# e-book_schema.net
KiCad netlist of a schematic drawn in EAGLE
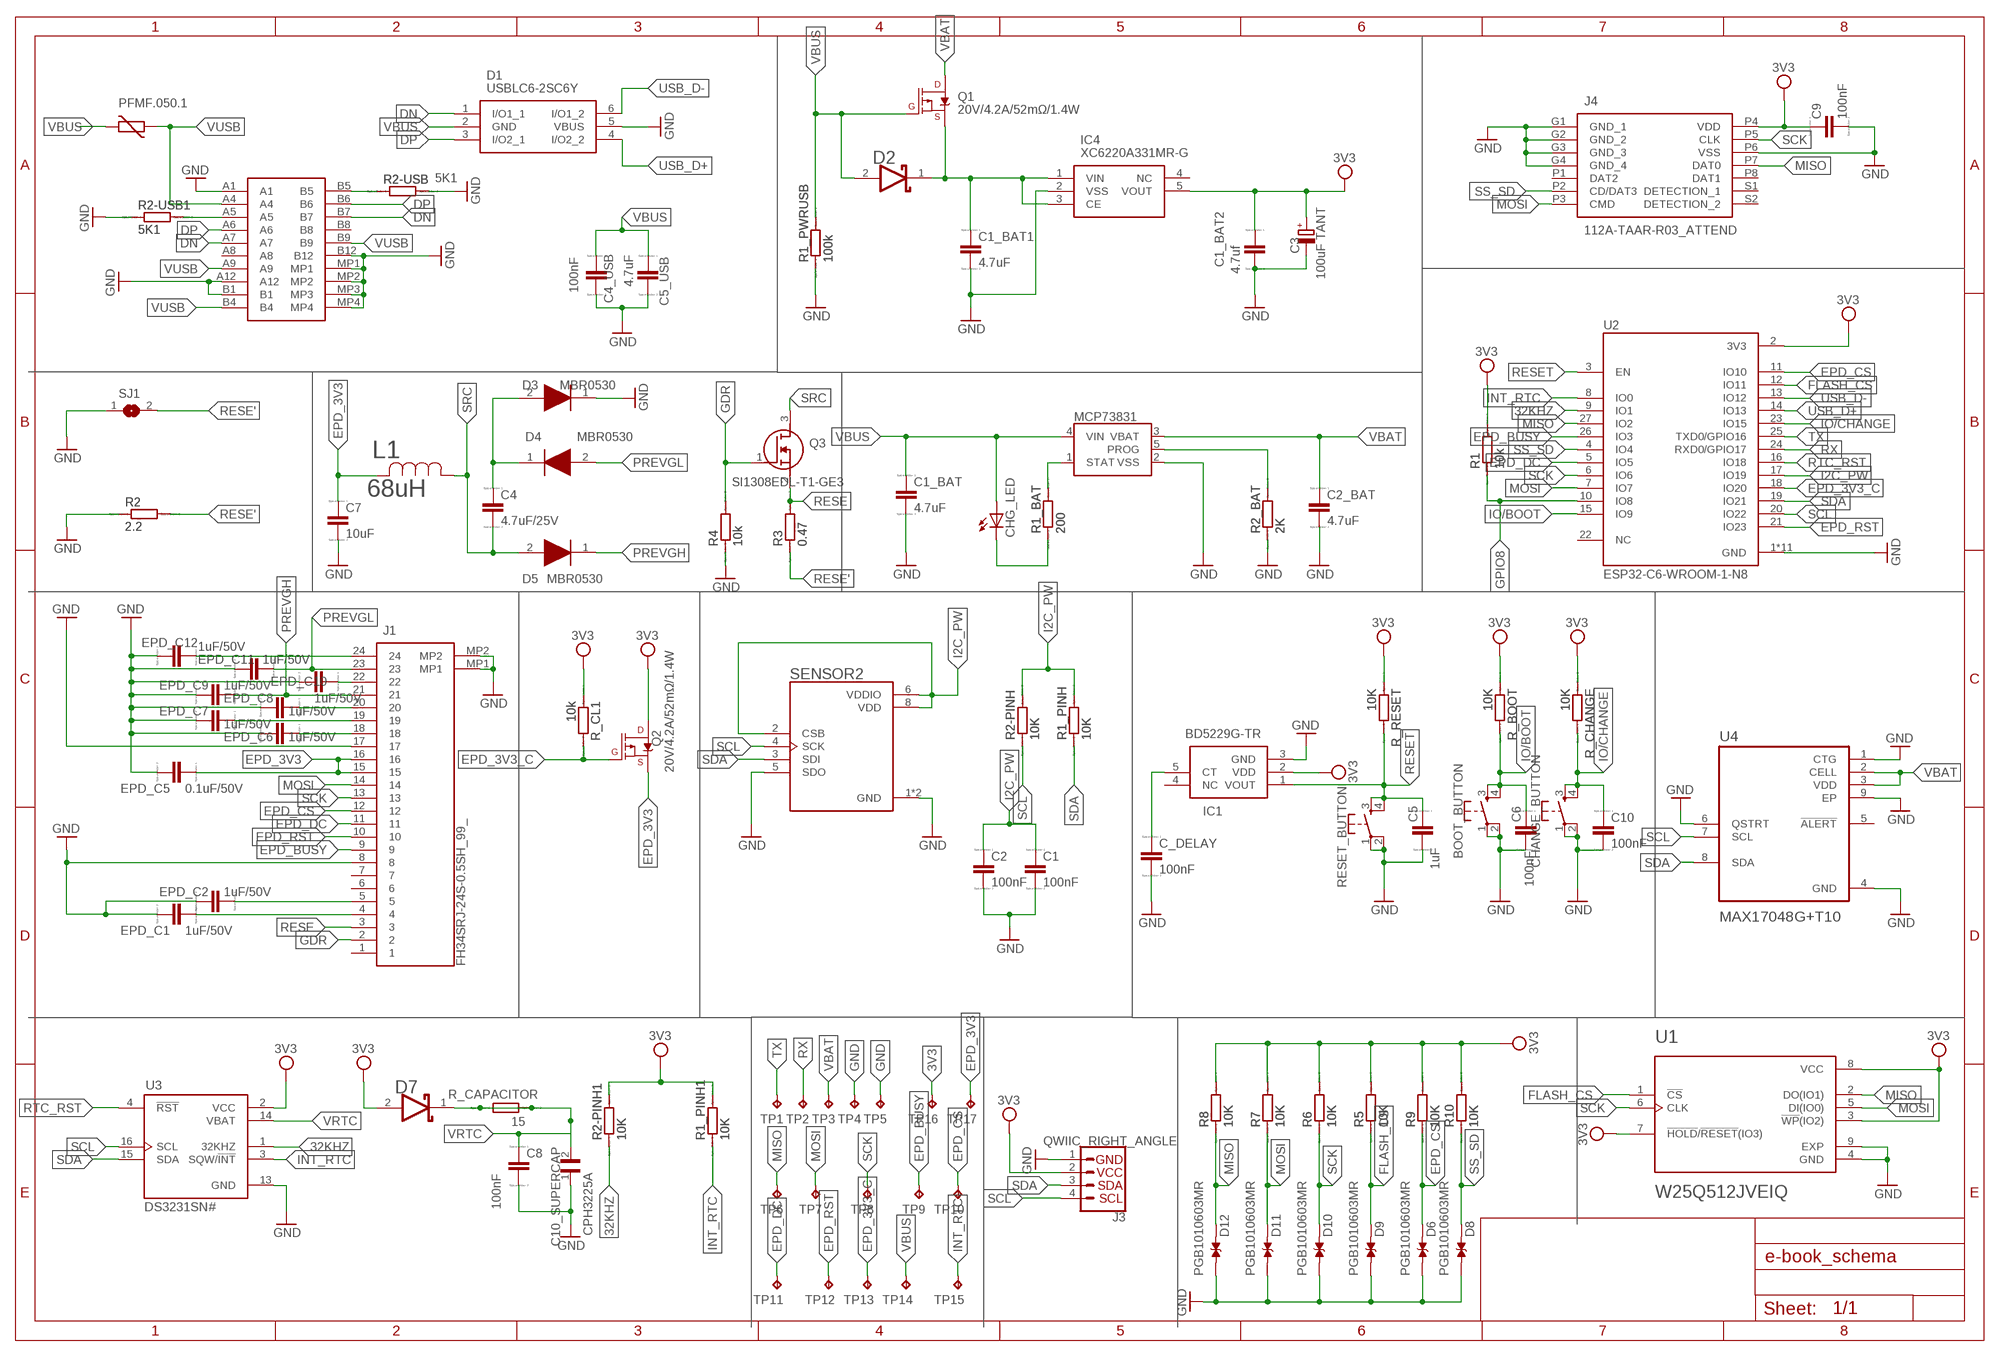
[diagram p0: schematic, sheet 1]

(export (version "E")
  (design (tool "Eeschema 10.0.6"))
  (components
    (comp (ref "BOOT_BUTTON")
      (value "BUTTON_CUSYOMV1")
      (footprint "eagle-import:MYBUTTON")
      (libsource (lib "eagle-import") (part "BUTTON_CUSYOMV1"))
    )
    (comp (ref "C1")
      (value "100nF")
      (footprint "eagle-import:EAGLE-LTSPICE_C0402")
      (libsource (lib "eagle-import") (part "EAGLE-LTSPICE_CC0402"))
    )
    (comp (ref "C1_BAT")
      (value "4.7uF")
      (footprint "eagle-import:EAGLE-LTSPICE_C0402")
      (libsource (lib "eagle-import") (part "EAGLE-LTSPICE_CC0402"))
    )
    (comp (ref "C1_BAT1")
      (value "4.7uF")
      (footprint "eagle-import:EAGLE-LTSPICE_C0402")
      (libsource (lib "eagle-import") (part "EAGLE-LTSPICE_CC0402"))
    )
    (comp (ref "C1_BAT2")
      (value "4.7uf")
      (footprint "eagle-import:EAGLE-LTSPICE_C0402")
      (libsource (lib "eagle-import") (part "EAGLE-LTSPICE_CC0402"))
    )
    (comp (ref "C2")
      (value "100nF")
      (footprint "eagle-import:EAGLE-LTSPICE_C0402")
      (libsource (lib "eagle-import") (part "EAGLE-LTSPICE_CC0402"))
    )
    (comp (ref "C2_BAT")
      (value "4.7uF")
      (footprint "eagle-import:EAGLE-LTSPICE_C0402")
      (libsource (lib "eagle-import") (part "EAGLE-LTSPICE_CC0402"))
    )
    (comp (ref "C3")
      (value "100uF TANT")
      (footprint "eagle-import:RCL_CT3528")
      (libsource (lib "eagle-import") (part "RCL_CPOL-EUCT3528"))
    )
    (comp (ref "C4")
      (value "4.7uF/25V")
      (footprint "eagle-import:EAGLE-LTSPICE_C0402")
      (libsource (lib "eagle-import") (part "EAGLE-LTSPICE_CC0402"))
    )
    (comp (ref "C4_USB")
      (value "100nF")
      (footprint "eagle-import:EAGLE-LTSPICE_C0402")
      (libsource (lib "eagle-import") (part "EAGLE-LTSPICE_CC0402"))
    )
    (comp (ref "C5")
      (value "1uF")
      (footprint "eagle-import:EAGLE-LTSPICE_C0402")
      (libsource (lib "eagle-import") (part "EAGLE-LTSPICE_CC0402"))
    )
    (comp (ref "C5_USB")
      (value "4.7uF")
      (footprint "eagle-import:EAGLE-LTSPICE_C0402")
      (libsource (lib "eagle-import") (part "EAGLE-LTSPICE_CC0402"))
    )
    (comp (ref "C6")
      (value "100nF")
      (footprint "eagle-import:EAGLE-LTSPICE_C0402")
      (libsource (lib "eagle-import") (part "EAGLE-LTSPICE_CC0402"))
    )
    (comp (ref "C7")
      (value "10uF")
      (footprint "eagle-import:EAGLE-LTSPICE_C0402")
      (libsource (lib "eagle-import") (part "EAGLE-LTSPICE_CC0402"))
    )
    (comp (ref "C8")
      (value "100nF")
      (footprint "eagle-import:EAGLE-LTSPICE_C0402")
      (libsource (lib "eagle-import") (part "EAGLE-LTSPICE_CC0402"))
    )
    (comp (ref "C9")
      (value "100nF")
      (footprint "eagle-import:EAGLE-LTSPICE_C0402")
      (libsource (lib "eagle-import") (part "EAGLE-LTSPICE_CC0402"))
    )
    (comp (ref "C10")
      (value "100nF")
      (footprint "eagle-import:EAGLE-LTSPICE_C0402")
      (libsource (lib "eagle-import") (part "EAGLE-LTSPICE_CC0402"))
    )
    (comp (ref "C10_SUPERCAP")
      (value "CPH3225A")
      (footprint "eagle-import:CAPCP3225X100N")
      (fields (field (name "MF") "Seiko Instruments"))
      (libsource (lib "eagle-import") (part "CPH3225A"))
    )
    (comp (ref "CHANGE_BUTTON")
      (value "BUTTON_CUSYOMV1")
      (footprint "eagle-import:MYBUTTON")
      (libsource (lib "eagle-import") (part "BUTTON_CUSYOMV1"))
    )
    (comp (ref "CHG_LED")
      (value "ADAFRUIT_LEDCHIP-LED0603")
      (footprint "eagle-import:ADAFRUIT_CHIP-LED0603")
      (libsource (lib "eagle-import") (part "ADAFRUIT_LEDCHIP-LED0603"))
    )
    (comp (ref "C_DELAY")
      (value "100nF")
      (footprint "eagle-import:EAGLE-LTSPICE_C0402")
      (libsource (lib "eagle-import") (part "EAGLE-LTSPICE_CC0402"))
    )
    (comp (ref "D1")
      (value "USBLC6-2SC6Y")
      (footprint "eagle-import:SOT95P280X145-6N")
      (fields (field (name "MF") "STMicroelectronics"))
      (libsource (lib "eagle-import") (part "USBLC6-2SC6Y"))
    )
    (comp (ref "D2")
      (value "ESP32_WROVER_AVX---SD0805S020S1R0_AVX_SD0805S020S1R0_0_0AVX_SD0805S020S1R0_0_0")
      (footprint "eagle-import:ESP32_WROVER_AVX---SD0805S020S1R0_AVX_SD0805S020S1R0_0")
      (fields
        (field (name "DIGIKEY_PART_NUMBER") "478-7800-1-ND")
        (field (name "MF") "AVX")
        (field (name "MOUSER_PART_NUMBER") "581-SD0805S020S1R0")
      )
      (libsource (lib "eagle-import") (part "ESP32_WROVER_AVX---SD0805S020S1R0_AVX_SD0805S020S1R0_0_0AVX_SD0805S020S1R0_0_0"))
    )
    (comp (ref "D3")
      (value "MBR0530")
      (footprint "eagle-import:SOD3716X135N")
      (fields (field (name "MF") "ON Semiconductor"))
      (libsource (lib "eagle-import") (part "MBR0530"))
    )
    (comp (ref "D4")
      (value "MBR0530")
      (footprint "eagle-import:SOD3716X135N")
      (fields (field (name "MF") "ON Semiconductor"))
      (libsource (lib "eagle-import") (part "MBR0530"))
    )
    (comp (ref "D5")
      (value "MBR0530")
      (footprint "eagle-import:SOD3716X135N")
      (fields (field (name "MF") "ON Semiconductor"))
      (libsource (lib "eagle-import") (part "MBR0530"))
    )
    (comp (ref "D6")
      (value "PGB1010603MR")
      (footprint "eagle-import:DIOC1608X36N")
      (fields (field (name "MF") "Littelfuse Inc."))
      (libsource (lib "eagle-import") (part "PGB1010603MR"))
    )
    (comp (ref "D7")
      (value "ESP32_WROVER_AVX---SD0805S020S1R0_AVX_SD0805S020S1R0_0_0AVX_SD0805S020S1R0_0_0")
      (footprint "eagle-import:ESP32_WROVER_AVX---SD0805S020S1R0_AVX_SD0805S020S1R0_0")
      (fields
        (field (name "DIGIKEY_PART_NUMBER") "478-7800-1-ND")
        (field (name "MF") "AVX")
        (field (name "MOUSER_PART_NUMBER") "581-SD0805S020S1R0")
      )
      (libsource (lib "eagle-import") (part "ESP32_WROVER_AVX---SD0805S020S1R0_AVX_SD0805S020S1R0_0_0AVX_SD0805S020S1R0_0_0"))
    )
    (comp (ref "D8")
      (value "PGB1010603MR")
      (footprint "eagle-import:DIOC1608X36N")
      (fields (field (name "MF") "Littelfuse Inc."))
      (libsource (lib "eagle-import") (part "PGB1010603MR"))
    )
    (comp (ref "D9")
      (value "PGB1010603MR")
      (footprint "eagle-import:DIOC1608X36N")
      (fields (field (name "MF") "Littelfuse Inc."))
      (libsource (lib "eagle-import") (part "PGB1010603MR"))
    )
    (comp (ref "D10")
      (value "PGB1010603MR")
      (footprint "eagle-import:DIOC1608X36N")
      (fields (field (name "MF") "Littelfuse Inc."))
      (libsource (lib "eagle-import") (part "PGB1010603MR"))
    )
    (comp (ref "D11")
      (value "PGB1010603MR")
      (footprint "eagle-import:DIOC1608X36N")
      (fields (field (name "MF") "Littelfuse Inc."))
      (libsource (lib "eagle-import") (part "PGB1010603MR"))
    )
    (comp (ref "D12")
      (value "PGB1010603MR")
      (footprint "eagle-import:DIOC1608X36N")
      (fields (field (name "MF") "Littelfuse Inc."))
      (libsource (lib "eagle-import") (part "PGB1010603MR"))
    )
    (comp (ref "EPD_C1")
      (value "1uF/50V")
      (footprint "eagle-import:EAGLE-LTSPICE_C0402")
      (libsource (lib "eagle-import") (part "EAGLE-LTSPICE_CC0402"))
    )
    (comp (ref "EPD_C2")
      (value "1uF/50V")
      (footprint "eagle-import:EAGLE-LTSPICE_C0402")
      (libsource (lib "eagle-import") (part "EAGLE-LTSPICE_CC0402"))
    )
    (comp (ref "EPD_C5")
      (value "0.1uF/50V")
      (footprint "eagle-import:EAGLE-LTSPICE_C0402")
      (libsource (lib "eagle-import") (part "EAGLE-LTSPICE_CC0402"))
    )
    (comp (ref "EPD_C6")
      (value "1uF/50V")
      (footprint "eagle-import:EAGLE-LTSPICE_C0402")
      (libsource (lib "eagle-import") (part "EAGLE-LTSPICE_CC0402"))
    )
    (comp (ref "EPD_C7")
      (value "1uF/50V")
      (footprint "eagle-import:EAGLE-LTSPICE_C0402")
      (libsource (lib "eagle-import") (part "EAGLE-LTSPICE_CC0402"))
    )
    (comp (ref "EPD_C8")
      (value "1uF/50V")
      (footprint "eagle-import:EAGLE-LTSPICE_C0402")
      (libsource (lib "eagle-import") (part "EAGLE-LTSPICE_CC0402"))
    )
    (comp (ref "EPD_C9")
      (value "1uF/50V")
      (footprint "eagle-import:EAGLE-LTSPICE_C0402")
      (libsource (lib "eagle-import") (part "EAGLE-LTSPICE_CC0402"))
    )
    (comp (ref "EPD_C10")
      (value "1uF/50V")
      (footprint "eagle-import:EAGLE-LTSPICE_C0402")
      (libsource (lib "eagle-import") (part "EAGLE-LTSPICE_CC0402"))
    )
    (comp (ref "EPD_C11")
      (value "1uF/50V")
      (footprint "eagle-import:EAGLE-LTSPICE_C0402")
      (libsource (lib "eagle-import") (part "EAGLE-LTSPICE_CC0402"))
    )
    (comp (ref "EPD_C12")
      (value "1uF/50V")
      (footprint "eagle-import:EAGLE-LTSPICE_C0402")
      (libsource (lib "eagle-import") (part "EAGLE-LTSPICE_CC0402"))
    )
    (comp (ref "IC1")
      (value "BD5229G-TR")
      (footprint "eagle-import:SOT95P280X125-5N")
      (fields (field (name "MOUSER_PART_NUMBER") "755-BD5229G-TR"))
      (libsource (lib "eagle-import") (part "BD5229G-TR"))
    )
    (comp (ref "IC4")
      (value "XC6220A331MR-G")
      (footprint "eagle-import:SOT95P280X120-5N")
      (fields (field (name "MOUSER_PART_NUMBER") "865-XC6220A331MR-G"))
      (libsource (lib "eagle-import") (part "XC6220A331MR-G"))
    )
    (comp (ref "J1")
      (value "FH34SRJ-24S-0.5SH_99_")
      (footprint "eagle-import:FH34SRJ24S05SH99")
      (fields
        (field (name "MANUFACTURER_PART_NUMBER") "FH34SRJ-24S-0.5SH(99)")
        (field (name "MOUSER_PART_NUMBER") "798-FH34SRJ24S05SH99")
      )
      (libsource (lib "eagle-import") (part "FH34SRJ-24S-0.5SH_99_"))
    )
    (comp (ref "J2")
      (value "SAMACSYS_PARTS_USB4110-GF-A")
      (footprint "eagle-import:SAMACSYS_PARTS_USB4110GFA")
      (fields
        (field (name "MANUFACTURER_PART_NUMBER") "USB4110-GF-A")
        (field (name "MOUSER_PART_NUMBER") "640-USB4110-GF-A")
      )
      (libsource (lib "eagle-import") (part "SAMACSYS_PARTS_USB4110-GF-A"))
    )
    (comp (ref "J3")
      (value "QWIIC_RIGHT_ANGLE")
      (footprint "eagle-import:JST04_1MM_RA")
      (libsource (lib "eagle-import") (part "QWIIC_CONNECTORJS-1MM"))
    )
    (comp (ref "J4")
      (value "112A-TAAR-R03_ATTEND")
      (footprint "eagle-import:112ATAARR03ATTEND")
      (fields (field (name "MANUFACTURER_PART_NUMBER") "112A-TAAR-R03 ATTEND"))
      (libsource (lib "eagle-import") (part "112A-TAAR-R03_ATTEND"))
    )
    (comp (ref "L1")
      (value "68uH")
      (footprint "eagle-import:IND_4828-WE-TPC_WRE")
      (fields
        (field (name "MANUFACTURER_PART_NUMBER") "744043680")
        (field (name "COPYRIGHT") "Copyright (C) 2024 Ultra Librarian. All rights reserved.")
      )
      (libsource (lib "eagle-import") (part "744043680IND_4828-WE-TPC_WRE"))
    )
    (comp (ref "MCP73831")
      (value "ESP32_WROVER_SPARKFUN-IC-POWER_MCP73831")
      (footprint "eagle-import:ESP32_WROVER_SPARKFUN-IC-POWER_SOT23-5")
      (libsource (lib "eagle-import") (part "ESP32_WROVER_SPARKFUN-IC-POWER_MCP73831"))
    )
    (comp (ref "PFMF.050.1")
      (value "ESP32C6_VARISTORCN1812")
      (footprint "eagle-import:ESP32C6_VARISTOR_CT_CN1812")
      (libsource (lib "eagle-import") (part "ESP32C6_VARISTORCN1812"))
    )
    (comp (ref "Q1")
      (value "20V/4.2A/52mΩ/1.4W")
      (footprint "eagle-import:ESP32_WROVER_SPARKFUN-DISCRETESEMI_SOT23-3")
      (libsource (lib "eagle-import") (part "ESP32_WROVER_SPARKFUN-DISCRETESEMI_MOSFET_PCH-DMG2305UX-7"))
    )
    (comp (ref "Q2")
      (value "20V/4.2A/52mΩ/1.4W")
      (footprint "eagle-import:ESP32_WROVER_SPARKFUN-DISCRETESEMI_SOT23-3")
      (libsource (lib "eagle-import") (part "ESP32_WROVER_SPARKFUN-DISCRETESEMI_MOSFET_PCH-DMG2305UX-7"))
    )
    (comp (ref "Q3")
      (value "SI1308EDL-T1-GE3")
      (footprint "eagle-import:SOT65P210X110-3N")
      (fields (field (name "MF") "Vishay Siliconix"))
      (libsource (lib "eagle-import") (part "SI1308EDL-T1-GE3"))
    )
    (comp (ref "R1")
      (value "10k")
      (footprint "eagle-import:ESP32_WROVER_EAGLE-LTSPICE_R0402")
      (libsource (lib "eagle-import") (part "ESP32_WROVER_EAGLE-LTSPICE_RR0402"))
    )
    (comp (ref "R1_BAT")
      (value "200")
      (footprint "eagle-import:ESP32_WROVER_EAGLE-LTSPICE_R0402")
      (libsource (lib "eagle-import") (part "ESP32_WROVER_EAGLE-LTSPICE_RR0402"))
    )
    (comp (ref "R1_PINH")
      (value "10K")
      (footprint "eagle-import:ESP32_WROVER_EAGLE-LTSPICE_R0402")
      (libsource (lib "eagle-import") (part "ESP32_WROVER_EAGLE-LTSPICE_RR0402"))
    )
    (comp (ref "R1_PINH1")
      (value "10K")
      (footprint "eagle-import:ESP32_WROVER_EAGLE-LTSPICE_R0402")
      (libsource (lib "eagle-import") (part "ESP32_WROVER_EAGLE-LTSPICE_RR0402"))
    )
    (comp (ref "R1_PWRUSB")
      (value "100k")
      (footprint "eagle-import:ESP32_WROVER_EAGLE-LTSPICE_R0402")
      (libsource (lib "eagle-import") (part "ESP32_WROVER_EAGLE-LTSPICE_RR0402"))
    )
    (comp (ref "R2")
      (value "2.2")
      (footprint "eagle-import:ESP32_WROVER_EAGLE-LTSPICE_R0402")
      (libsource (lib "eagle-import") (part "ESP32_WROVER_EAGLE-LTSPICE_RR0402"))
    )
    (comp (ref "R2-PINH")
      (value "10K")
      (footprint "eagle-import:ESP32_WROVER_EAGLE-LTSPICE_R0402")
      (libsource (lib "eagle-import") (part "ESP32_WROVER_EAGLE-LTSPICE_RR0402"))
    )
    (comp (ref "R2-PINH1")
      (value "10K")
      (footprint "eagle-import:ESP32_WROVER_EAGLE-LTSPICE_R0402")
      (libsource (lib "eagle-import") (part "ESP32_WROVER_EAGLE-LTSPICE_RR0402"))
    )
    (comp (ref "R2-USB")
      (value "5K1")
      (footprint "eagle-import:ESP32_WROVER_EAGLE-LTSPICE_R0402")
      (libsource (lib "eagle-import") (part "ESP32_WROVER_EAGLE-LTSPICE_RR0402"))
    )
    (comp (ref "R2-USB1")
      (value "5K1")
      (footprint "eagle-import:ESP32_WROVER_EAGLE-LTSPICE_R0402")
      (libsource (lib "eagle-import") (part "ESP32_WROVER_EAGLE-LTSPICE_RR0402"))
    )
    (comp (ref "R2_BAT")
      (value "2K")
      (footprint "eagle-import:ESP32_WROVER_EAGLE-LTSPICE_R0402")
      (libsource (lib "eagle-import") (part "ESP32_WROVER_EAGLE-LTSPICE_RR0402"))
    )
    (comp (ref "R3")
      (value "0.47")
      (footprint "eagle-import:ESP32_WROVER_EAGLE-LTSPICE_R0402")
      (libsource (lib "eagle-import") (part "ESP32_WROVER_EAGLE-LTSPICE_RR0402"))
    )
    (comp (ref "R4")
      (value "10k")
      (footprint "eagle-import:ESP32_WROVER_EAGLE-LTSPICE_R0402")
      (libsource (lib "eagle-import") (part "ESP32_WROVER_EAGLE-LTSPICE_RR0402"))
    )
    (comp (ref "R5")
      (value "10K")
      (footprint "eagle-import:ESP32_WROVER_EAGLE-LTSPICE_R0402")
      (libsource (lib "eagle-import") (part "ESP32_WROVER_EAGLE-LTSPICE_RR0402"))
    )
    (comp (ref "R6")
      (value "10K")
      (footprint "eagle-import:ESP32_WROVER_EAGLE-LTSPICE_R0402")
      (libsource (lib "eagle-import") (part "ESP32_WROVER_EAGLE-LTSPICE_RR0402"))
    )
    (comp (ref "R7")
      (value "10K")
      (footprint "eagle-import:ESP32_WROVER_EAGLE-LTSPICE_R0402")
      (libsource (lib "eagle-import") (part "ESP32_WROVER_EAGLE-LTSPICE_RR0402"))
    )
    (comp (ref "R8")
      (value "10K")
      (footprint "eagle-import:ESP32_WROVER_EAGLE-LTSPICE_R0402")
      (libsource (lib "eagle-import") (part "ESP32_WROVER_EAGLE-LTSPICE_RR0402"))
    )
    (comp (ref "R9")
      (value "10K")
      (footprint "eagle-import:ESP32_WROVER_EAGLE-LTSPICE_R0402")
      (libsource (lib "eagle-import") (part "ESP32_WROVER_EAGLE-LTSPICE_RR0402"))
    )
    (comp (ref "R10")
      (value "10K")
      (footprint "eagle-import:ESP32_WROVER_EAGLE-LTSPICE_R0402")
      (libsource (lib "eagle-import") (part "ESP32_WROVER_EAGLE-LTSPICE_RR0402"))
    )
    (comp (ref "RESET_BUTTON")
      (value "BUTTON_CUSYOMV1")
      (footprint "eagle-import:MYBUTTON")
      (libsource (lib "eagle-import") (part "BUTTON_CUSYOMV1"))
    )
    (comp (ref "R_BOOT")
      (value "10K")
      (footprint "eagle-import:ESP32_WROVER_EAGLE-LTSPICE_R0402")
      (libsource (lib "eagle-import") (part "ESP32_WROVER_EAGLE-LTSPICE_RR0402"))
    )
    (comp (ref "R_CAPACITOR")
      (value "15")
      (footprint "eagle-import:ESP32_WROVER_EAGLE-LTSPICE_R0402")
      (libsource (lib "eagle-import") (part "ESP32_WROVER_EAGLE-LTSPICE_RR0402"))
    )
    (comp (ref "R_CHANGE")
      (value "10K")
      (footprint "eagle-import:ESP32_WROVER_EAGLE-LTSPICE_R0402")
      (libsource (lib "eagle-import") (part "ESP32_WROVER_EAGLE-LTSPICE_RR0402"))
    )
    (comp (ref "R_CL1")
      (value "10k")
      (footprint "eagle-import:ESP32_WROVER_EAGLE-LTSPICE_R0402")
      (libsource (lib "eagle-import") (part "ESP32_WROVER_EAGLE-LTSPICE_RR0402"))
    )
    (comp (ref "R_RESET")
      (value "10K")
      (footprint "eagle-import:ESP32_WROVER_EAGLE-LTSPICE_R0402")
      (libsource (lib "eagle-import") (part "ESP32_WROVER_EAGLE-LTSPICE_RR0402"))
    )
    (comp (ref "SENSOR2")
      (value "ESP32_WROVER_BME680_BME680")
      (footprint "eagle-import:ESP32_WROVER_BME680_PSON80P300X300X100-8N")
      (fields (field (name "MF") "Bosch Sensortec") (field (name "MP") "BME680"))
      (libsource (lib "eagle-import") (part "ESP32_WROVER_BME680_BME680"))
    )
    (comp (ref "SJ1") (value "SJ") (footprint "eagle-import:SJ") (libsource (lib "eagle-import") (part "SJ")))
    (comp (ref "TP1")
      (value "TPTP20R")
      (footprint "eagle-import:TP20R")
      (libsource (lib "eagle-import") (part "TPTP20R"))
    )
    (comp (ref "TP2")
      (value "TPTP20R")
      (footprint "eagle-import:TP20R")
      (libsource (lib "eagle-import") (part "TPTP20R"))
    )
    (comp (ref "TP3")
      (value "TPTP20R")
      (footprint "eagle-import:TP20R")
      (libsource (lib "eagle-import") (part "TPTP20R"))
    )
    (comp (ref "TP4")
      (value "TPTP20R")
      (footprint "eagle-import:TP20R")
      (libsource (lib "eagle-import") (part "TPTP20R"))
    )
    (comp (ref "TP5")
      (value "TPTP20R")
      (footprint "eagle-import:TP20R")
      (libsource (lib "eagle-import") (part "TPTP20R"))
    )
    (comp (ref "TP6")
      (value "TPTP20R")
      (footprint "eagle-import:TP20R")
      (libsource (lib "eagle-import") (part "TPTP20R"))
    )
    (comp (ref "TP7")
      (value "TPTP20R")
      (footprint "eagle-import:TP20R")
      (libsource (lib "eagle-import") (part "TPTP20R"))
    )
    (comp (ref "TP8")
      (value "TPTP20R")
      (footprint "eagle-import:TP20R")
      (libsource (lib "eagle-import") (part "TPTP20R"))
    )
    (comp (ref "TP9")
      (value "TPTP20R")
      (footprint "eagle-import:TP20R")
      (libsource (lib "eagle-import") (part "TPTP20R"))
    )
    (comp (ref "TP10")
      (value "TPTP20R")
      (footprint "eagle-import:TP20R")
      (libsource (lib "eagle-import") (part "TPTP20R"))
    )
    (comp (ref "TP11")
      (value "TPTP20R")
      (footprint "eagle-import:TP20R")
      (libsource (lib "eagle-import") (part "TPTP20R"))
    )
    (comp (ref "TP12")
      (value "TPTP20R")
      (footprint "eagle-import:TP20R")
      (libsource (lib "eagle-import") (part "TPTP20R"))
    )
    (comp (ref "TP13")
      (value "TPTP20R")
      (footprint "eagle-import:TP20R")
      (libsource (lib "eagle-import") (part "TPTP20R"))
    )
    (comp (ref "TP14")
      (value "TPTP20R")
      (footprint "eagle-import:TP20R")
      (libsource (lib "eagle-import") (part "TPTP20R"))
    )
    (comp (ref "TP15")
      (value "TPTP20R")
      (footprint "eagle-import:TP20R")
      (libsource (lib "eagle-import") (part "TPTP20R"))
    )
    (comp (ref "TP16")
      (value "TPTP20R")
      (footprint "eagle-import:TP20R")
      (libsource (lib "eagle-import") (part "TPTP20R"))
    )
    (comp (ref "TP17")
      (value "TPTP20R")
      (footprint "eagle-import:TP20R")
      (libsource (lib "eagle-import") (part "TPTP20R"))
    )
    (comp (ref "U1")
      (value "W25Q512JVEIQ")
      (footprint "eagle-import:SON127P600X800X80-9N")
      (fields (field (name "MF") "Winbond Electronics"))
      (libsource (lib "eagle-import") (part "W25Q512JVEIQ"))
    )
    (comp (ref "U2")
      (value "ESP32-C6-WROOM-1-N8")
      (footprint "eagle-import:XCVR_ESP32-C6-WROOM-1-N8")
      (fields (field (name "MF") "Espressif Systems"))
      (libsource (lib "eagle-import") (part "ESP32-C6-WROOM-1-N8"))
    )
    (comp (ref "U3")
      (value "DS3231SN#")
      (footprint "eagle-import:SOIC127P1032X265-16N")
      (fields (field (name "MF") "Analog Devices"))
      (libsource (lib "eagle-import") (part "DS3231SN#"))
    )
    (comp (ref "U4")
      (value "MAX17048G+T10")
      (footprint "eagle-import:SON50P200X200X80-9N")
      (fields (field (name "MF") "Analog Devices"))
      (libsource (lib "eagle-import") (part "MAX17048G+T10"))
    )
  )
  (nets
    (net (code "1") (name "3V3") (class "Default")
      (node (ref "C1_BAT2") (pin "1") (pinfunction "1_1") (pintype "passive"))
      (node (ref "C3") (pin "+") (pinfunction "+_+") (pintype "passive"))
      (node (ref "C9") (pin "1") (pinfunction "1_1") (pintype "passive"))
      (node (ref "D7") (pin "2") (pinfunction "ANODE_2") (pintype "bidirectional"))
      (node (ref "IC1") (pin "2") (pinfunction "VDD_2") (pintype "bidirectional"))
      (node (ref "IC4") (pin "5") (pinfunction "VOUT_5") (pintype "bidirectional"))
      (node (ref "J3") (pin "2") (pinfunction "2_2") (pintype "power_in"))
      (node (ref "J4") (pin "P4") (pinfunction "VDD_P4") (pintype "bidirectional"))
      (node (ref "Q2") (pin "3") (pinfunction "D_3") (pintype "bidirectional"))
      (node (ref "R1") (pin "2") (pinfunction "2_2") (pintype "passive"))
      (node (ref "R10") (pin "2") (pinfunction "2_2") (pintype "passive"))
      (node (ref "R1_PINH1") (pin "2") (pinfunction "2_2") (pintype "passive"))
      (node (ref "R2-PINH1") (pin "2") (pinfunction "2_2") (pintype "passive"))
      (node (ref "R5") (pin "2") (pinfunction "2_2") (pintype "passive"))
      (node (ref "R6") (pin "2") (pinfunction "2_2") (pintype "passive"))
      (node (ref "R7") (pin "2") (pinfunction "2_2") (pintype "passive"))
      (node (ref "R8") (pin "2") (pinfunction "2_2") (pintype "passive"))
      (node (ref "R9") (pin "2") (pinfunction "2_2") (pintype "passive"))
      (node (ref "R_BOOT") (pin "1") (pinfunction "1_1") (pintype "passive"))
      (node (ref "R_CHANGE") (pin "1") (pinfunction "1_1") (pintype "passive"))
      (node (ref "R_CL1") (pin "1") (pinfunction "1_1") (pintype "passive"))
      (node (ref "R_RESET") (pin "1") (pinfunction "1_1") (pintype "passive"))
      (node (ref "TP16") (pin "TP") (pinfunction "TP_TP") (pintype "input"))
      (node (ref "U1") (pin "3") (pinfunction "~{WP}(IO2)_3") (pintype "bidirectional"))
      (node (ref "U1") (pin "7") (pinfunction "~{HOLD}/~{RESET}(IO3)_7") (pintype "bidirectional"))
      (node (ref "U1") (pin "8") (pinfunction "VCC_8") (pintype "power_in"))
      (node (ref "U2") (pin "2") (pinfunction "3V3_2") (pintype "power_in"))
      (node (ref "U3") (pin "2") (pinfunction "VCC_2") (pintype "power_in"))
    )
    (net (code "2") (name "32KHZ") (class "Default")
      (node (ref "R2-PINH1") (pin "1") (pinfunction "1_1") (pintype "passive"))
      (node (ref "U2") (pin "9") (pinfunction "IO1_9") (pintype "bidirectional"))
      (node (ref "U3") (pin "1") (pinfunction "32KHZ_1") (pintype "output"))
    )
    (net (code "3") (name "DN") (class "Default")
      (node (ref "D1") (pin "1") (pinfunction "I/O1_1_1") (pintype "bidirectional"))
      (node (ref "J2") (pin "A7") (pinfunction "A7_A7") (pintype "bidirectional"))
      (node (ref "J2") (pin "B7") (pinfunction "B7_B7") (pintype "bidirectional"))
    )
    (net (code "4") (name "DP") (class "Default")
      (node (ref "D1") (pin "3") (pinfunction "I/O2_1_3") (pintype "bidirectional"))
      (node (ref "J2") (pin "A6") (pinfunction "A6_A6") (pintype "bidirectional"))
      (node (ref "J2") (pin "B6") (pinfunction "B6_B6") (pintype "bidirectional"))
    )
    (net (code "5") (name "EPD_3V3") (class "Default")
      (node (ref "C7") (pin "1") (pinfunction "1_1") (pintype "passive"))
      (node (ref "EPD_C5") (pin "1") (pinfunction "1_1") (pintype "passive"))
      (node (ref "J1") (pin "15") (pinfunction "15_15") (pintype "bidirectional"))
      (node (ref "J1") (pin "16") (pinfunction "16_16") (pintype "bidirectional"))
      (node (ref "L1") (pin "2") (pinfunction "2_2") (pintype "passive"))
      (node (ref "Q2") (pin "2") (pinfunction "S_2") (pintype "bidirectional"))
      (node (ref "TP17") (pin "TP") (pinfunction "TP_TP") (pintype "input"))
    )
    (net (code "6") (name "EPD_3V3_C") (class "Default")
      (node (ref "Q2") (pin "1") (pinfunction "G_1") (pintype "bidirectional"))
      (node (ref "R_CL1") (pin "2") (pinfunction "2_2") (pintype "passive"))
      (node (ref "TP13") (pin "TP") (pinfunction "TP_TP") (pintype "input"))
      (node (ref "U2") (pin "18") (pinfunction "IO20_18") (pintype "bidirectional"))
    )
    (net (code "7") (name "EPD_BUSY") (class "Default")
      (node (ref "J1") (pin "9") (pinfunction "9_9") (pintype "bidirectional"))
      (node (ref "TP9") (pin "TP") (pinfunction "TP_TP") (pintype "input"))
      (node (ref "U2") (pin "26") (pinfunction "IO3_26") (pintype "bidirectional"))
    )
    (net (code "8") (name "EPD_CS") (class "Default")
      (node (ref "D6") (pin "2") (pinfunction "2_2") (pintype "passive"))
      (node (ref "J1") (pin "12") (pinfunction "12_12") (pintype "bidirectional"))
      (node (ref "R9") (pin "1") (pinfunction "1_1") (pintype "passive"))
      (node (ref "TP10") (pin "TP") (pinfunction "TP_TP") (pintype "input"))
      (node (ref "U2") (pin "11") (pinfunction "IO10_11") (pintype "bidirectional"))
    )
    (net (code "9") (name "EPD_DC") (class "Default")
      (node (ref "J1") (pin "11") (pinfunction "11_11") (pintype "bidirectional"))
      (node (ref "TP11") (pin "TP") (pinfunction "TP_TP") (pintype "input"))
      (node (ref "U2") (pin "5") (pinfunction "IO5_5") (pintype "bidirectional"))
    )
    (net (code "10") (name "EPD_RST") (class "Default")
      (node (ref "J1") (pin "10") (pinfunction "10_10") (pintype "bidirectional"))
      (node (ref "TP12") (pin "TP") (pinfunction "TP_TP") (pintype "input"))
      (node (ref "U2") (pin "21") (pinfunction "IO23_21") (pintype "bidirectional"))
    )
    (net (code "11") (name "FLASH_CS") (class "Default")
      (node (ref "D9") (pin "2") (pinfunction "2_2") (pintype "passive"))
      (node (ref "R5") (pin "1") (pinfunction "1_1") (pintype "passive"))
      (node (ref "U1") (pin "1") (pinfunction "~{CS}_1") (pintype "input"))
      (node (ref "U2") (pin "12") (pinfunction "IO11_12") (pintype "bidirectional"))
    )
    (net (code "12") (name "GDR") (class "Default")
      (node (ref "J1") (pin "2") (pinfunction "2_2") (pintype "bidirectional"))
      (node (ref "Q3") (pin "1") (pinfunction "G_1") (pintype "bidirectional"))
      (node (ref "R4") (pin "2") (pinfunction "2_2") (pintype "passive"))
    )
    (net (code "13") (name "GND") (class "Default")
      (node (ref "BOOT_BUTTON") (pin "1") (pinfunction "1_1") (pintype "passive"))
      (node (ref "BOOT_BUTTON") (pin "2") (pinfunction "2_2") (pintype "passive"))
      (node (ref "C1") (pin "2") (pinfunction "2_2") (pintype "passive"))
      (node (ref "C10") (pin "2") (pinfunction "2_2") (pintype "passive"))
      (node (ref "C10_SUPERCAP") (pin "1") (pinfunction "1_1") (pintype "passive"))
      (node (ref "C1_BAT") (pin "2") (pinfunction "2_2") (pintype "passive"))
      (node (ref "C1_BAT1") (pin "2") (pinfunction "2_2") (pintype "passive"))
      (node (ref "C1_BAT2") (pin "2") (pinfunction "2_2") (pintype "passive"))
      (node (ref "C2") (pin "2") (pinfunction "2_2") (pintype "passive"))
      (node (ref "C2_BAT") (pin "2") (pinfunction "2_2") (pintype "passive"))
      (node (ref "C3") (pin "-") (pinfunction "-_-") (pintype "passive"))
      (node (ref "C4_USB") (pin "2") (pinfunction "2_2") (pintype "passive"))
      (node (ref "C5") (pin "2") (pinfunction "2_2") (pintype "passive"))
      (node (ref "C5_USB") (pin "2") (pinfunction "2_2") (pintype "passive"))
      (node (ref "C6") (pin "2") (pinfunction "2_2") (pintype "passive"))
      (node (ref "C7") (pin "2") (pinfunction "2_2") (pintype "passive"))
      (node (ref "C8") (pin "2") (pinfunction "2_2") (pintype "passive"))
      (node (ref "C9") (pin "2") (pinfunction "2_2") (pintype "passive"))
      (node (ref "CHANGE_BUTTON") (pin "1") (pinfunction "1_1") (pintype "passive"))
      (node (ref "CHANGE_BUTTON") (pin "2") (pinfunction "2_2") (pintype "passive"))
      (node (ref "C_DELAY") (pin "2") (pinfunction "2_2") (pintype "passive"))
      (node (ref "D1") (pin "5") (pinfunction "VBUS_5") (pintype "bidirectional"))
      (node (ref "D10") (pin "1") (pinfunction "1_1") (pintype "passive"))
      (node (ref "D11") (pin "1") (pinfunction "1_1") (pintype "passive"))
      (node (ref "D12") (pin "1") (pinfunction "1_1") (pintype "passive"))
      (node (ref "D3") (pin "1") (pinfunction "K_1") (pintype "bidirectional"))
      (node (ref "D6") (pin "1") (pinfunction "1_1") (pintype "passive"))
      (node (ref "D8") (pin "1") (pinfunction "1_1") (pintype "passive"))
      (node (ref "D9") (pin "1") (pinfunction "1_1") (pintype "passive"))
      (node (ref "EPD_C1") (pin "2") (pinfunction "2_2") (pintype "passive"))
      (node (ref "EPD_C10") (pin "2") (pinfunction "2_2") (pintype "passive"))
      (node (ref "EPD_C11") (pin "2") (pinfunction "2_2") (pintype "passive"))
      (node (ref "EPD_C12") (pin "2") (pinfunction "2_2") (pintype "passive"))
      (node (ref "EPD_C2") (pin "2") (pinfunction "2_2") (pintype "passive"))
      (node (ref "EPD_C5") (pin "2") (pinfunction "2_2") (pintype "passive"))
      (node (ref "EPD_C6") (pin "2") (pinfunction "2_2") (pintype "passive"))
      (node (ref "EPD_C7") (pin "2") (pinfunction "2_2") (pintype "passive"))
      (node (ref "EPD_C8") (pin "2") (pinfunction "2_2") (pintype "passive"))
      (node (ref "EPD_C9") (pin "2") (pinfunction "2_2") (pintype "passive"))
      (node (ref "IC1") (pin "3") (pinfunction "GND_3") (pintype "bidirectional"))
      (node (ref "IC4") (pin "2") (pinfunction "VSS_2") (pintype "bidirectional"))
      (node (ref "J1") (pin "17") (pinfunction "17_17") (pintype "bidirectional"))
      (node (ref "J1") (pin "8") (pinfunction "8_8") (pintype "bidirectional"))
      (node (ref "J1") (pin "MP1") (pinfunction "MP1_MP1") (pintype "bidirectional"))
      (node (ref "J1") (pin "MP2") (pinfunction "MP2_MP2") (pintype "bidirectional"))
      (node (ref "J2") (pin "A1") (pinfunction "A1_A1") (pintype "bidirectional"))
      (node (ref "J2") (pin "A12") (pinfunction "A12_A12") (pintype "bidirectional"))
      (node (ref "J2") (pin "B1") (pinfunction "B1_B1") (pintype "bidirectional"))
      (node (ref "J2") (pin "B12") (pinfunction "B12_B12") (pintype "bidirectional"))
      (node (ref "J2") (pin "MP1") (pinfunction "MP1_MP1") (pintype "bidirectional"))
      (node (ref "J2") (pin "MP2") (pinfunction "MP2_MP2") (pintype "bidirectional"))
      (node (ref "J2") (pin "MP3") (pinfunction "MP3_MP3") (pintype "bidirectional"))
      (node (ref "J2") (pin "MP4") (pinfunction "MP4_MP4") (pintype "bidirectional"))
      (node (ref "J3") (pin "1") (pinfunction "1_1") (pintype "power_in"))
      (node (ref "J4") (pin "G1") (pinfunction "GND_1_G1") (pintype "bidirectional"))
      (node (ref "J4") (pin "G2") (pinfunction "GND_2_G2") (pintype "bidirectional"))
      (node (ref "J4") (pin "G3") (pinfunction "GND_3_G3") (pintype "bidirectional"))
      (node (ref "J4") (pin "G4") (pinfunction "GND_4_G4") (pintype "bidirectional"))
      (node (ref "J4") (pin "P6") (pinfunction "VSS_P6") (pintype "bidirectional"))
      (node (ref "MCP73831") (pin "2") (pinfunction "VSS_2") (pintype "power_in"))
      (node (ref "R1_PWRUSB") (pin "1") (pinfunction "1_1") (pintype "passive"))
      (node (ref "R2") (pin "1") (pinfunction "1_1") (pintype "passive"))
      (node (ref "R2-USB") (pin "2") (pinfunction "2_2") (pintype "passive"))
      (node (ref "R2-USB1") (pin "1") (pinfunction "1_1") (pintype "passive"))
      (node (ref "R2_BAT") (pin "1") (pinfunction "1_1") (pintype "passive"))
      (node (ref "R4") (pin "1") (pinfunction "1_1") (pintype "passive"))
      (node (ref "RESET_BUTTON") (pin "1") (pinfunction "1_1") (pintype "passive"))
      (node (ref "RESET_BUTTON") (pin "2") (pinfunction "2_2") (pintype "passive"))
      (node (ref "SENSOR2") (pin "1") (pinfunction "GND_1") (pintype "power_in"))
      (node (ref "SENSOR2") (pin "5") (pinfunction "SDO_5") (pintype "bidirectional"))
      (node (ref "SENSOR2") (pin "7") (pinfunction "GND_7") (pintype "power_in"))
      (node (ref "SJ1") (pin "1") (pinfunction "1_1") (pintype "passive"))
      (node (ref "TP4") (pin "TP") (pinfunction "TP_TP") (pintype "input"))
      (node (ref "TP5") (pin "TP") (pinfunction "TP_TP") (pintype "input"))
      (node (ref "U1") (pin "4") (pinfunction "GND_4") (pintype "power_in"))
      (node (ref "U1") (pin "9") (pinfunction "EXP_9") (pintype "passive"))
      (node (ref "U2") (pin "1") (pinfunction "GND_1") (pintype "power_in"))
      (node (ref "U2") (pin "28") (pinfunction "GND_28") (pintype "power_in"))
      (node (ref "U2") (pin "29_1") (pinfunction "GND_29_1") (pintype "power_in"))
      (node (ref "U2") (pin "29_2") (pinfunction "GND_29_2") (pintype "power_in"))
      (node (ref "U2") (pin "29_3") (pinfunction "GND_29_3") (pintype "power_in"))
      (node (ref "U2") (pin "29_4") (pinfunction "GND_29_4") (pintype "power_in"))
      (node (ref "U2") (pin "29_5") (pinfunction "GND_29_5") (pintype "power_in"))
      (node (ref "U2") (pin "29_6") (pinfunction "GND_29_6") (pintype "power_in"))
      (node (ref "U2") (pin "29_7") (pinfunction "GND_29_7") (pintype "power_in"))
      (node (ref "U2") (pin "29_8") (pinfunction "GND_29_8") (pintype "power_in"))
      (node (ref "U2") (pin "29_9") (pinfunction "GND_29_9") (pintype "power_in"))
      (node (ref "U3") (pin "13") (pinfunction "GND_13") (pintype "power_in"))
      (node (ref "U4") (pin "1") (pinfunction "CTG_1") (pintype "power_in"))
      (node (ref "U4") (pin "4") (pinfunction "GND_4") (pintype "power_in"))
      (node (ref "U4") (pin "6") (pinfunction "QSTRT_6") (pintype "input"))
      (node (ref "U4") (pin "9") (pinfunction "EP_9") (pintype "power_in"))
    )
    (net (code "14") (name "GPIO8") (class "Default")
      (node (ref "R1") (pin "1") (pinfunction "1_1") (pintype "passive"))
      (node (ref "U2") (pin "10") (pinfunction "IO8_10") (pintype "bidirectional"))
    )
    (net (code "15") (name "I2C_PW") (class "Default")
      (node (ref "C1") (pin "1") (pinfunction "1_1") (pintype "passive"))
      (node (ref "C2") (pin "1") (pinfunction "1_1") (pintype "passive"))
      (node (ref "R1_PINH") (pin "2") (pinfunction "2_2") (pintype "passive"))
      (node (ref "R2-PINH") (pin "2") (pinfunction "2_2") (pintype "passive"))
      (node (ref "SENSOR2") (pin "2") (pinfunction "CSB_2") (pintype "input"))
      (node (ref "SENSOR2") (pin "6") (pinfunction "VDDIO_6") (pintype "power_in"))
      (node (ref "SENSOR2") (pin "8") (pinfunction "VDD_8") (pintype "power_in"))
      (node (ref "U2") (pin "17") (pinfunction "IO19_17") (pintype "bidirectional"))
    )
    (net (code "16") (name "INT_RTC") (class "Default")
      (node (ref "R1_PINH1") (pin "1") (pinfunction "1_1") (pintype "passive"))
      (node (ref "TP15") (pin "TP") (pinfunction "TP_TP") (pintype "input"))
      (node (ref "U2") (pin "8") (pinfunction "IO0_8") (pintype "bidirectional"))
      (node (ref "U3") (pin "3") (pinfunction "SQW/~{INT}_3") (pintype "output"))
    )
    (net (code "17") (name "IO{slash}BOOT") (class "Default")
      (node (ref "BOOT_BUTTON") (pin "3") (pinfunction "3_3") (pintype "passive"))
      (node (ref "BOOT_BUTTON") (pin "4") (pinfunction "4_4") (pintype "passive"))
      (node (ref "C6") (pin "1") (pinfunction "1_1") (pintype "passive"))
      (node (ref "R_BOOT") (pin "2") (pinfunction "2_2") (pintype "passive"))
      (node (ref "U2") (pin "15") (pinfunction "IO9_15") (pintype "bidirectional"))
    )
    (net (code "18") (name "IO{slash}CHANGE") (class "Default")
      (node (ref "C10") (pin "1") (pinfunction "1_1") (pintype "passive"))
      (node (ref "CHANGE_BUTTON") (pin "3") (pinfunction "3_3") (pintype "passive"))
      (node (ref "CHANGE_BUTTON") (pin "4") (pinfunction "4_4") (pintype "passive"))
      (node (ref "R_CHANGE") (pin "2") (pinfunction "2_2") (pintype "passive"))
      (node (ref "U2") (pin "23") (pinfunction "IO15_23") (pintype "bidirectional"))
    )
    (net (code "19") (name "MISO") (class "Default")
      (node (ref "D12") (pin "2") (pinfunction "2_2") (pintype "passive"))
      (node (ref "J4") (pin "P7") (pinfunction "DAT0_P7") (pintype "bidirectional"))
      (node (ref "R8") (pin "1") (pinfunction "1_1") (pintype "passive"))
      (node (ref "TP6") (pin "TP") (pinfunction "TP_TP") (pintype "input"))
      (node (ref "U1") (pin "2") (pinfunction "DO(IO1)_2") (pintype "bidirectional"))
      (node (ref "U2") (pin "27") (pinfunction "IO2_27") (pintype "bidirectional"))
    )
    (net (code "20") (name "MOSI") (class "Default")
      (node (ref "D11") (pin "2") (pinfunction "2_2") (pintype "passive"))
      (node (ref "J1") (pin "14") (pinfunction "14_14") (pintype "bidirectional"))
      (node (ref "J4") (pin "P3") (pinfunction "CMD_P3") (pintype "bidirectional"))
      (node (ref "R7") (pin "1") (pinfunction "1_1") (pintype "passive"))
      (node (ref "TP7") (pin "TP") (pinfunction "TP_TP") (pintype "input"))
      (node (ref "U1") (pin "5") (pinfunction "DI(IO0)_5") (pintype "bidirectional"))
      (node (ref "U2") (pin "7") (pinfunction "IO7_7") (pintype "bidirectional"))
    )
    (net (code "21") (name "Net-(CHG_LED-PadC)") (class "Default")
      (node (ref "CHG_LED") (pin "C") (pinfunction "C_C") (pintype "passive"))
      (node (ref "R1_BAT") (pin "1") (pinfunction "1_1") (pintype "passive"))
    )
    (net (code "22") (name "Net-(D2-CATHODE)") (class "Default")
      (node (ref "C1_BAT1") (pin "1") (pinfunction "1_1") (pintype "passive"))
      (node (ref "D2") (pin "1") (pinfunction "CATHODE_1") (pintype "bidirectional"))
      (node (ref "IC4") (pin "1") (pinfunction "VIN_1") (pintype "bidirectional"))
      (node (ref "IC4") (pin "3") (pinfunction "CE_3") (pintype "bidirectional"))
      (node (ref "Q1") (pin "2") (pinfunction "S_2") (pintype "bidirectional"))
    )
    (net (code "23") (name "Net-(D3-A)") (class "Default")
      (node (ref "C4") (pin "1") (pinfunction "1_1") (pintype "passive"))
      (node (ref "D3") (pin "2") (pinfunction "A_2") (pintype "bidirectional"))
      (node (ref "D4") (pin "1") (pinfunction "K_1") (pintype "bidirectional"))
    )
    (net (code "24") (name "Net-(EPD_C1-Pad1)") (class "Default")
      (node (ref "EPD_C1") (pin "1") (pinfunction "1_1") (pintype "passive"))
      (node (ref "J1") (pin "4") (pinfunction "4_4") (pintype "bidirectional"))
    )
    (net (code "25") (name "Net-(EPD_C2-Pad1)") (class "Default")
      (node (ref "EPD_C2") (pin "1") (pinfunction "1_1") (pintype "passive"))
      (node (ref "J1") (pin "5") (pinfunction "5_5") (pintype "bidirectional"))
    )
    (net (code "26") (name "Net-(EPD_C6-Pad1)") (class "Default")
      (node (ref "EPD_C6") (pin "1") (pinfunction "1_1") (pintype "passive"))
      (node (ref "J1") (pin "18") (pinfunction "18_18") (pintype "bidirectional"))
    )
    (net (code "27") (name "Net-(EPD_C7-Pad1)") (class "Default")
      (node (ref "EPD_C7") (pin "1") (pinfunction "1_1") (pintype "passive"))
      (node (ref "J1") (pin "19") (pinfunction "19_19") (pintype "bidirectional"))
    )
    (net (code "28") (name "Net-(EPD_C8-Pad1)") (class "Default")
      (node (ref "EPD_C8") (pin "1") (pinfunction "1_1") (pintype "passive"))
      (node (ref "J1") (pin "20") (pinfunction "20_20") (pintype "bidirectional"))
    )
    (net (code "29") (name "Net-(EPD_C10-Pad1)") (class "Default")
      (node (ref "EPD_C10") (pin "1") (pinfunction "1_1") (pintype "passive"))
      (node (ref "J1") (pin "22") (pinfunction "22_22") (pintype "bidirectional"))
    )
    (net (code "30") (name "Net-(EPD_C12-Pad1)") (class "Default")
      (node (ref "EPD_C12") (pin "1") (pinfunction "1_1") (pintype "passive"))
      (node (ref "J1") (pin "24") (pinfunction "24_24") (pintype "bidirectional"))
    )
    (net (code "31") (name "Net-(IC1-CT)") (class "Default")
      (node (ref "C_DELAY") (pin "1") (pinfunction "1_1") (pintype "passive"))
      (node (ref "IC1") (pin "5") (pinfunction "CT_5") (pintype "bidirectional"))
    )
    (net (code "32") (name "Net-(J2-PadA5)") (class "Default")
      (node (ref "J2") (pin "A5") (pinfunction "A5_A5") (pintype "bidirectional"))
      (node (ref "R2-USB1") (pin "2") (pinfunction "2_2") (pintype "passive"))
    )
    (net (code "33") (name "Net-(J2-PadB5)") (class "Default")
      (node (ref "J2") (pin "B5") (pinfunction "B5_B5") (pintype "bidirectional"))
      (node (ref "R2-USB") (pin "1") (pinfunction "1_1") (pintype "passive"))
    )
    (net (code "34") (name "Net-(MCP73831-PROG)") (class "Default")
      (node (ref "MCP73831") (pin "5") (pinfunction "PROG_5") (pintype "input"))
      (node (ref "R2_BAT") (pin "2") (pinfunction "2_2") (pintype "passive"))
    )
    (net (code "35") (name "Net-(MCP73831-STAT)") (class "Default")
      (node (ref "MCP73831") (pin "1") (pinfunction "STAT_1") (pintype "output"))
      (node (ref "R1_BAT") (pin "2") (pinfunction "2_2") (pintype "passive"))
    )
    (net (code "36") (name "PREVGH") (class "Default")
      (node (ref "D5") (pin "1") (pinfunction "K_1") (pintype "bidirectional"))
      (node (ref "EPD_C9") (pin "1") (pinfunction "1_1") (pintype "passive"))
      (node (ref "J1") (pin "21") (pinfunction "21_21") (pintype "bidirectional"))
    )
    (net (code "37") (name "PREVGL") (class "Default")
      (node (ref "D4") (pin "2") (pinfunction "A_2") (pintype "bidirectional"))
      (node (ref "EPD_C11") (pin "1") (pinfunction "1_1") (pintype "passive"))
      (node (ref "J1") (pin "23") (pinfunction "23_23") (pintype "bidirectional"))
    )
    (net (code "38") (name "RESE") (class "Default")
      (node (ref "J1") (pin "3") (pinfunction "3_3") (pintype "bidirectional"))
      (node (ref "Q3") (pin "2") (pinfunction "S_2") (pintype "bidirectional"))
      (node (ref "R3") (pin "2") (pinfunction "2_2") (pintype "passive"))
    )
    (net (code "39") (name "RESE'") (class "Default")
      (node (ref "R2") (pin "2") (pinfunction "2_2") (pintype "passive"))
      (node (ref "R3") (pin "1") (pinfunction "1_1") (pintype "passive"))
      (node (ref "SJ1") (pin "2") (pinfunction "2_2") (pintype "passive"))
    )
    (net (code "40") (name "RESET") (class "Default")
      (node (ref "C5") (pin "1") (pinfunction "1_1") (pintype "passive"))
      (node (ref "IC1") (pin "1") (pinfunction "VOUT_1") (pintype "bidirectional"))
      (node (ref "RESET_BUTTON") (pin "3") (pinfunction "3_3") (pintype "passive"))
      (node (ref "RESET_BUTTON") (pin "4") (pinfunction "4_4") (pintype "passive"))
      (node (ref "R_RESET") (pin "2") (pinfunction "2_2") (pintype "passive"))
      (node (ref "U2") (pin "3") (pinfunction "EN_3") (pintype "input"))
    )
    (net (code "41") (name "RTC_RST") (class "Default")
      (node (ref "U2") (pin "16") (pinfunction "IO18_16") (pintype "bidirectional"))
      (node (ref "U3") (pin "4") (pinfunction "~{RST}_4") (pintype "input"))
    )
    (net (code "42") (name "RX") (class "Default")
      (node (ref "TP2") (pin "TP") (pinfunction "TP_TP") (pintype "input"))
      (node (ref "U2") (pin "24") (pinfunction "RXD0/GPIO17_24") (pintype "bidirectional"))
    )
    (net (code "43") (name "SCK") (class "Default")
      (node (ref "D10") (pin "2") (pinfunction "2_2") (pintype "passive"))
      (node (ref "J1") (pin "13") (pinfunction "13_13") (pintype "bidirectional"))
      (node (ref "J4") (pin "P5") (pinfunction "CLK_P5") (pintype "bidirectional"))
      (node (ref "R6") (pin "1") (pinfunction "1_1") (pintype "passive"))
      (node (ref "TP8") (pin "TP") (pinfunction "TP_TP") (pintype "input"))
      (node (ref "U1") (pin "6") (pinfunction "CLK_6") (pintype "input"))
      (node (ref "U2") (pin "6") (pinfunction "IO6_6") (pintype "bidirectional"))
    )
    (net (code "44") (name "SCL") (class "Default")
      (node (ref "J3") (pin "4") (pinfunction "4_4") (pintype "passive"))
      (node (ref "R2-PINH") (pin "1") (pinfunction "1_1") (pintype "passive"))
      (node (ref "SENSOR2") (pin "4") (pinfunction "SCK_4") (pintype "input"))
      (node (ref "U2") (pin "20") (pinfunction "IO22_20") (pintype "bidirectional"))
      (node (ref "U3") (pin "16") (pinfunction "SCL_16") (pintype "input"))
      (node (ref "U4") (pin "7") (pinfunction "SCL_7") (pintype "input"))
    )
    (net (code "45") (name "SDA") (class "Default")
      (node (ref "J3") (pin "3") (pinfunction "3_3") (pintype "passive"))
      (node (ref "R1_PINH") (pin "1") (pinfunction "1_1") (pintype "passive"))
      (node (ref "SENSOR2") (pin "3") (pinfunction "SDI_3") (pintype "bidirectional"))
      (node (ref "U2") (pin "19") (pinfunction "IO21_19") (pintype "bidirectional"))
      (node (ref "U3") (pin "15") (pinfunction "SDA_15") (pintype "bidirectional"))
      (node (ref "U4") (pin "8") (pinfunction "SDA_8") (pintype "bidirectional"))
    )
    (net (code "46") (name "SRC") (class "Default")
      (node (ref "C4") (pin "2") (pinfunction "2_2") (pintype "passive"))
      (node (ref "D5") (pin "2") (pinfunction "A_2") (pintype "bidirectional"))
      (node (ref "L1") (pin "1") (pinfunction "1_1") (pintype "passive"))
      (node (ref "Q3") (pin "3") (pinfunction "D_3") (pintype "bidirectional"))
    )
    (net (code "47") (name "SS_SD") (class "Default")
      (node (ref "D8") (pin "2") (pinfunction "2_2") (pintype "passive"))
      (node (ref "J4") (pin "P2") (pinfunction "CD/DAT3_P2") (pintype "bidirectional"))
      (node (ref "R10") (pin "1") (pinfunction "1_1") (pintype "passive"))
      (node (ref "U2") (pin "4") (pinfunction "IO4_4") (pintype "bidirectional"))
    )
    (net (code "48") (name "TX") (class "Default")
      (node (ref "TP1") (pin "TP") (pinfunction "TP_TP") (pintype "input"))
      (node (ref "U2") (pin "25") (pinfunction "TXD0/GPIO16_25") (pintype "bidirectional"))
    )
    (net (code "49") (name "USB_D+") (class "Default")
      (node (ref "D1") (pin "4") (pinfunction "I/O2_2_4") (pintype "bidirectional"))
      (node (ref "U2") (pin "14") (pinfunction "IO13_14") (pintype "bidirectional"))
    )
    (net (code "50") (name "USB_D-") (class "Default")
      (node (ref "D1") (pin "6") (pinfunction "I/O1_2_6") (pintype "bidirectional"))
      (node (ref "U2") (pin "13") (pinfunction "IO12_13") (pintype "bidirectional"))
    )
    (net (code "51") (name "VBAT") (class "Default")
      (node (ref "C2_BAT") (pin "1") (pinfunction "1_1") (pintype "passive"))
      (node (ref "MCP73831") (pin "3") (pinfunction "VBAT_3") (pintype "power_in"))
      (node (ref "Q1") (pin "3") (pinfunction "D_3") (pintype "bidirectional"))
      (node (ref "TP3") (pin "TP") (pinfunction "TP_TP") (pintype "input"))
      (node (ref "U4") (pin "2") (pinfunction "CELL_2") (pintype "power_in"))
      (node (ref "U4") (pin "3") (pinfunction "VDD_3") (pintype "power_in"))
    )
    (net (code "52") (name "VBUS") (class "Default")
      (node (ref "C1_BAT") (pin "1") (pinfunction "1_1") (pintype "passive"))
      (node (ref "C4_USB") (pin "1") (pinfunction "1_1") (pintype "passive"))
      (node (ref "C5_USB") (pin "1") (pinfunction "1_1") (pintype "passive"))
      (node (ref "CHG_LED") (pin "A") (pinfunction "A_A") (pintype "passive"))
      (node (ref "D1") (pin "2") (pinfunction "GND_2") (pintype "bidirectional"))
      (node (ref "D2") (pin "2") (pinfunction "ANODE_2") (pintype "bidirectional"))
      (node (ref "MCP73831") (pin "4") (pinfunction "VIN_4") (pintype "power_in"))
      (node (ref "PFMF.050.1") (pin "2") (pinfunction "2_2") (pintype "passive"))
      (node (ref "Q1") (pin "1") (pinfunction "G_1") (pintype "bidirectional"))
      (node (ref "R1_PWRUSB") (pin "2") (pinfunction "2_2") (pintype "passive"))
      (node (ref "TP14") (pin "TP") (pinfunction "TP_TP") (pintype "input"))
    )
    (net (code "53") (name "VRTC") (class "Default")
      (node (ref "C10_SUPERCAP") (pin "2") (pinfunction "2_2") (pintype "passive"))
      (node (ref "C8") (pin "1") (pinfunction "1_1") (pintype "passive"))
      (node (ref "D7") (pin "1") (pinfunction "CATHODE_1") (pintype "bidirectional"))
      (node (ref "R_CAPACITOR") (pin "1") (pinfunction "1_1") (pintype "passive"))
      (node (ref "R_CAPACITOR") (pin "2") (pinfunction "2_2") (pintype "passive"))
      (node (ref "U3") (pin "14") (pinfunction "VBAT_14") (pintype "power_in"))
    )
    (net (code "54") (name "VUSB") (class "Default")
      (node (ref "J2") (pin "A4") (pinfunction "A4_A4") (pintype "bidirectional"))
      (node (ref "J2") (pin "A9") (pinfunction "A9_A9") (pintype "bidirectional"))
      (node (ref "J2") (pin "B4") (pinfunction "B4_B4") (pintype "bidirectional"))
      (node (ref "J2") (pin "B9") (pinfunction "B9_B9") (pintype "bidirectional"))
      (node (ref "PFMF.050.1") (pin "1") (pinfunction "1_1") (pintype "passive"))
    )
    (net (code "55") (name "unconnected-(IC1-NC-Pad4)") (class "Default")
      (node (ref "IC1") (pin "4") (pinfunction "NC_4") (pintype "no_connect"))
    )
    (net (code "56") (name "unconnected-(IC4-NC-Pad4)") (class "Default")
      (node (ref "IC4") (pin "4") (pinfunction "NC_4") (pintype "no_connect"))
    )
    (net (code "57") (name "unconnected-(J1-Pad1)") (class "Default")
      (node (ref "J1") (pin "1") (pinfunction "1_1") (pintype "bidirectional"))
    )
    (net (code "58") (name "unconnected-(J1-Pad6)") (class "Default")
      (node (ref "J1") (pin "6") (pinfunction "6_6") (pintype "bidirectional"))
    )
    (net (code "59") (name "unconnected-(J1-Pad7)") (class "Default")
      (node (ref "J1") (pin "7") (pinfunction "7_7") (pintype "bidirectional"))
    )
    (net (code "60") (name "unconnected-(J2-PadA8)") (class "Default")
      (node (ref "J2") (pin "A8") (pinfunction "A8_A8") (pintype "bidirectional"))
    )
    (net (code "61") (name "unconnected-(J2-PadB8)") (class "Default")
      (node (ref "J2") (pin "B8") (pinfunction "B8_B8") (pintype "bidirectional"))
    )
    (net (code "62") (name "unconnected-(J4-DAT1-PadP8)") (class "Default")
      (node (ref "J4") (pin "P8") (pinfunction "DAT1_P8") (pintype "bidirectional"))
    )
    (net (code "63") (name "unconnected-(J4-DAT2-PadP1)") (class "Default")
      (node (ref "J4") (pin "P1") (pinfunction "DAT2_P1") (pintype "bidirectional"))
    )
    (net (code "64") (name "unconnected-(J4-DETECTION_1-PadS1)") (class "Default")
      (node (ref "J4") (pin "S1") (pinfunction "DETECTION_1_S1") (pintype "bidirectional"))
    )
    (net (code "65") (name "unconnected-(J4-DETECTION_2-PadS2)") (class "Default")
      (node (ref "J4") (pin "S2") (pinfunction "DETECTION_2_S2") (pintype "bidirectional"))
    )
    (net (code "66") (name "unconnected-(U2-NC-Pad22)") (class "Default")
      (node (ref "U2") (pin "22") (pinfunction "NC_22") (pintype "no_connect"))
    )
    (net (code "67") (name "unconnected-(U4-~{ALERT}-Pad5)") (class "Default")
      (node (ref "U4") (pin "5") (pinfunction "~{ALERT}_5") (pintype "output"))
    )
  )
)
